# eeZeeProp.net
KiCad netlist of a schematic drawn in EAGLE
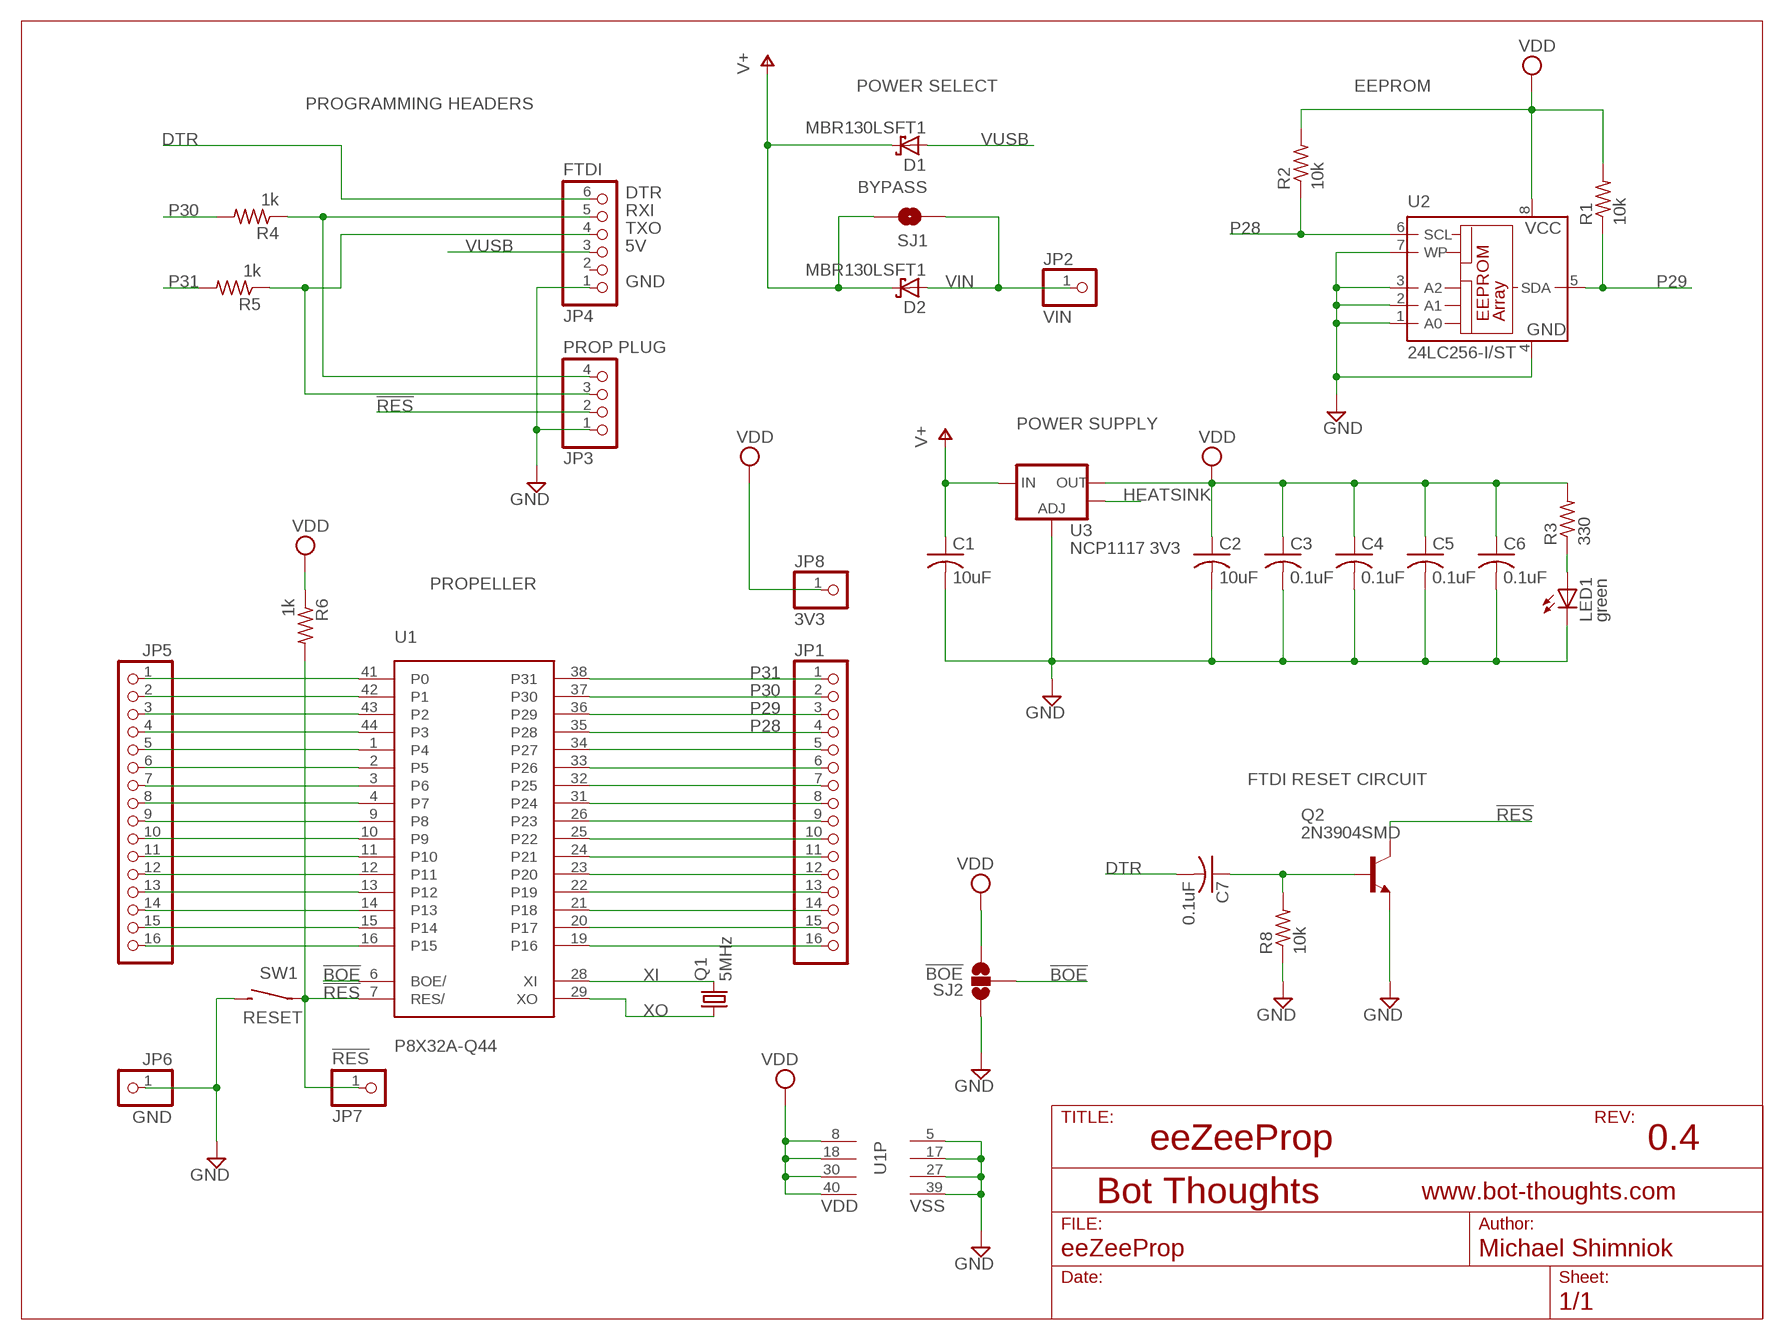
[diagram p0: schematic, sheet 1]

(export (version "E")
  (design (tool "Eeschema 10.0.6"))
  (components
    (comp (ref "C1")
      (value "10uF")
      (footprint "eagle-import:C1206")
      (fields (field (name "PARTNO") "T491A106M006AT"))
      (libsource (lib "eagle-import") (part "C-USC1206"))
    )
    (comp (ref "C2")
      (value "10uF")
      (footprint "eagle-import:C1206")
      (fields (field (name "PARTNO") "T491A106M006AT"))
      (libsource (lib "eagle-import") (part "C-USC1206"))
    )
    (comp (ref "C3")
      (value "0.1uF")
      (footprint "eagle-import:C0603")
      (fields (field (name "PARTNO") "0603YC104KAT2A"))
      (libsource (lib "eagle-import") (part "C-USC0603"))
    )
    (comp (ref "C4")
      (value "0.1uF")
      (footprint "eagle-import:C0603")
      (fields (field (name "PARTNO") "0603YC104KAT2A"))
      (libsource (lib "eagle-import") (part "C-USC0603"))
    )
    (comp (ref "C5")
      (value "0.1uF")
      (footprint "eagle-import:C0603")
      (fields (field (name "PARTNO") "0603YC104KAT2A"))
      (libsource (lib "eagle-import") (part "C-USC0603"))
    )
    (comp (ref "C6")
      (value "0.1uF")
      (footprint "eagle-import:C0603")
      (fields (field (name "PARTNO") "0603YC104KAT2A"))
      (libsource (lib "eagle-import") (part "C-USC0603"))
    )
    (comp (ref "C7")
      (value "0.1uF")
      (footprint "eagle-import:C0603")
      (fields (field (name "PARTNO") "0603YC104KAT2A"))
      (libsource (lib "eagle-import") (part "C-USC0603"))
    )
    (comp (ref "D1")
      (value "MBR130LSFT1")
      (footprint "eagle-import:SOD123FL")
      (fields (field (name "PARTNO") "MBR130LSFT1G"))
      (libsource (lib "eagle-import") (part "SCHOTTKY-DIODE-MBR130LSFT1"))
    )
    (comp (ref "D2")
      (value "MBR130LSFT1")
      (footprint "eagle-import:SOD123FL")
      (fields (field (name "PARTNO") "MBR130LSFT1G"))
      (libsource (lib "eagle-import") (part "SCHOTTKY-DIODE-MBR130LSFT1"))
    )
    (comp (ref "JP1")
      (value "PINHD-1X16_2.54-S")
      (footprint "eagle-import:1X16-S")
      (libsource (lib "eagle-import") (part "PINHD-1X16_2.54-S"))
    )
    (comp (ref "JP2")
      (value "VIN")
      (footprint "eagle-import:1X01")
      (libsource (lib "eagle-import") (part "PINHD-1X01_2.54"))
    )
    (comp (ref "JP3")
      (value "PROP PLUG")
      (footprint "eagle-import:1X04-S")
      (libsource (lib "eagle-import") (part "PINHD-1X04_2.54-S"))
    )
    (comp (ref "JP4")
      (value "FTDI")
      (footprint "eagle-import:1X06-S")
      (fields (field (name "PARTNO") "2211S-06G"))
      (libsource (lib "eagle-import") (part "PINHD-1X06_2.54-S"))
    )
    (comp (ref "JP5")
      (value "PINHD-1X16_2.54-S")
      (footprint "eagle-import:1X16-S")
      (libsource (lib "eagle-import") (part "PINHD-1X16_2.54-S"))
    )
    (comp (ref "JP6")
      (value "GND")
      (footprint "eagle-import:1X01")
      (libsource (lib "eagle-import") (part "PINHD-1X01_2.54"))
    )
    (comp (ref "JP7")
      (value "!RES")
      (footprint "eagle-import:1X01")
      (libsource (lib "eagle-import") (part "PINHD-1X01_2.54"))
    )
    (comp (ref "JP8")
      (value "3V3")
      (footprint "eagle-import:1X01")
      (libsource (lib "eagle-import") (part "PINHD-1X01_2.54"))
    )
    (comp (ref "LED1")
      (value "green")
      (footprint "eagle-import:CHIPLED_1206")
      (fields (field (name "PARTNO") "LG N971-KN-1"))
      (libsource (lib "eagle-import") (part "LEDCHIPLED_1206"))
    )
    (comp (ref "Q1")
      (value "5MHz")
      (footprint "eagle-import:HC49U-V")
      (fields (field (name "OC_FARNELL") "1666969") (field (name "PARTNO") "HC49US-5.000MABJ-UB"))
      (libsource (lib "eagle-import") (part "CRYSTALHC49U-V"))
    )
    (comp (ref "Q2")
      (value "2N3904SMD")
      (footprint "eagle-import:SOT-23")
      (fields (field (name "PARTNO") "MMBT3904LT3G"))
      (libsource (lib "eagle-import") (part "2N3904SMD"))
    )
    (comp (ref "R1")
      (value "10k")
      (footprint "eagle-import:R0603")
      (fields (field (name "PARTNO") "ERJ-3GEYJ103V"))
      (libsource (lib "eagle-import") (part "R-US_R0603"))
    )
    (comp (ref "R2")
      (value "10k")
      (footprint "eagle-import:R0603")
      (fields (field (name "PARTNO") "ERJ-3GEYJ103V"))
      (libsource (lib "eagle-import") (part "R-US_R0603"))
    )
    (comp (ref "R3")
      (value "330")
      (footprint "eagle-import:R0603")
      (fields (field (name "PARTNO") "ERJ-3GEYJ331V"))
      (libsource (lib "eagle-import") (part "R-US_R0603"))
    )
    (comp (ref "R4")
      (value "1k")
      (footprint "eagle-import:R0603")
      (fields (field (name "PARTNO") "RC0603JR-071KL"))
      (libsource (lib "eagle-import") (part "R-US_R0603"))
    )
    (comp (ref "R5")
      (value "1k")
      (footprint "eagle-import:R0603")
      (fields (field (name "PARTNO") "RC0603JR-071KL"))
      (libsource (lib "eagle-import") (part "R-US_R0603"))
    )
    (comp (ref "R6")
      (value "1k")
      (footprint "eagle-import:R0603")
      (fields (field (name "PARTNO") "RC0603JR-071KL"))
      (libsource (lib "eagle-import") (part "R-US_R0603"))
    )
    (comp (ref "R8")
      (value "10k")
      (footprint "eagle-import:R0603")
      (fields (field (name "PARTNO") "ERJ-3GEYJ103V"))
      (libsource (lib "eagle-import") (part "R-US_R0603"))
    )
    (comp (ref "SJ1")
      (value "BYPASS")
      (footprint "eagle-import:SJ_2S-NO")
      (libsource (lib "eagle-import") (part "SOLDERJUMPERNO"))
    )
    (comp (ref "SJ2")
      (value "!BOE")
      (footprint "eagle-import:SJ_3")
      (libsource (lib "eagle-import") (part "SOLDERJUMPER_2WAYS"))
    )
    (comp (ref "SW1")
      (value "RESET")
      (footprint "eagle-import:6MMTACTILE_RECT")
      (fields (field (name "PARTNO") "MJTP1243"))
      (libsource (lib "eagle-import") (part "SPST_TAC_RECT1"))
    )
    (comp (ref "U1")
      (value "P8X32A-Q44")
      (footprint "eagle-import:P8X32A-Q44")
      (fields (field (name "PARTNO") "P8X32A-Q44"))
      (libsource (lib "eagle-import") (part "P8X32A-Q44"))
    )
    (comp (ref "U2")
      (value "24LC256-I/ST")
      (footprint "eagle-import:SO-08")
      (fields
        (field (name "MF") "MICROCHIP")
        (field (name "MPN") "24LC128-I/SNG")
        (field (name "MF_1") "OnSemi")
        (field (name "MPN_1") "CAT24C256WI-GT3")
        (field (name "PARTNO") "CAT24C256WI-GT3")
      )
      (libsource (lib "eagle-import") (part "24SNLC128"))
    )
    (comp (ref "U3")
      (value "NCP1117 3V3")
      (footprint "eagle-import:SOT223")
      (fields (field (name "PARTNO") "NCP1117ST33T3G"))
      (libsource (lib "eagle-import") (part "V_REG_LM1117SOT223"))
    )
  )
  (nets
    (net (code "1") (name "/DTR") (class "Default")
      (node (ref "C7") (pin "2") (pinfunction "2_2") (pintype "passive"))
      (node (ref "JP4") (pin "6") (pinfunction "6_6") (pintype "passive"))
    )
    (net (code "2") (name "/HEATSINK") (class "Default")
      (node (ref "U3") (pin "4") (pinfunction "OUT_4") (pintype "output"))
    )
    (net (code "3") (name "/P28") (class "Default")
      (node (ref "JP1") (pin "4") (pinfunction "4_4") (pintype "passive"))
      (node (ref "R2") (pin "1") (pinfunction "1_1") (pintype "passive"))
      (node (ref "U1") (pin "35") (pinfunction "P28_35") (pintype "bidirectional"))
      (node (ref "U2") (pin "6") (pinfunction "SCL_6") (pintype "input"))
    )
    (net (code "4") (name "/P29") (class "Default")
      (node (ref "JP1") (pin "3") (pinfunction "3_3") (pintype "passive"))
      (node (ref "R1") (pin "1") (pinfunction "1_1") (pintype "passive"))
      (node (ref "U1") (pin "36") (pinfunction "P29_36") (pintype "bidirectional"))
      (node (ref "U2") (pin "5") (pinfunction "SDA_5") (pintype "bidirectional"))
    )
    (net (code "5") (name "/P30") (class "Default")
      (node (ref "JP1") (pin "2") (pinfunction "2_2") (pintype "passive"))
      (node (ref "R4") (pin "2") (pinfunction "2_2") (pintype "passive"))
      (node (ref "U1") (pin "37") (pinfunction "P30_37") (pintype "bidirectional"))
    )
    (net (code "6") (name "/P31") (class "Default")
      (node (ref "JP1") (pin "1") (pinfunction "1_1") (pintype "passive"))
      (node (ref "R5") (pin "2") (pinfunction "2_2") (pintype "passive"))
      (node (ref "U1") (pin "38") (pinfunction "P31_38") (pintype "bidirectional"))
    )
    (net (code "7") (name "/VIN") (class "Default")
      (node (ref "D2") (pin "A") (pinfunction "A_A") (pintype "passive"))
      (node (ref "JP2") (pin "1") (pinfunction "1_1") (pintype "passive"))
      (node (ref "SJ1") (pin "1") (pinfunction "1_1") (pintype "passive"))
    )
    (net (code "8") (name "/VUSB") (class "Default")
      (node (ref "D1") (pin "A") (pinfunction "A_A") (pintype "passive"))
      (node (ref "JP4") (pin "3") (pinfunction "3_3") (pintype "passive"))
    )
    (net (code "9") (name "/XI") (class "Default")
      (node (ref "Q1") (pin "2") (pinfunction "2_2") (pintype "passive"))
      (node (ref "U1") (pin "28") (pinfunction "XI_28") (pintype "input"))
    )
    (net (code "10") (name "/XO") (class "Default")
      (node (ref "Q1") (pin "1") (pinfunction "1_1") (pintype "passive"))
      (node (ref "U1") (pin "29") (pinfunction "XO_29") (pintype "output"))
    )
    (net (code "11") (name "/~{BOE}") (class "Default")
      (node (ref "SJ2") (pin "2") (pinfunction "2_2") (pintype "passive"))
      (node (ref "U1") (pin "6") (pinfunction "BOE/_6") (pintype "input"))
    )
    (net (code "12") (name "/~{RES}") (class "Default")
      (node (ref "JP3") (pin "2") (pinfunction "2_2") (pintype "passive"))
      (node (ref "JP7") (pin "1") (pinfunction "1_1") (pintype "passive"))
      (node (ref "Q2") (pin "1") (pinfunction "C_1") (pintype "passive"))
      (node (ref "R6") (pin "2") (pinfunction "2_2") (pintype "passive"))
      (node (ref "SW1") (pin "P$1") (pinfunction "P_P$1") (pintype "passive"))
      (node (ref "U1") (pin "7") (pinfunction "RES/_7") (pintype "bidirectional"))
    )
    (net (code "13") (name "GND") (class "Default")
      (node (ref "C1") (pin "2") (pinfunction "2_2") (pintype "passive"))
      (node (ref "C2") (pin "2") (pinfunction "2_2") (pintype "passive"))
      (node (ref "C3") (pin "2") (pinfunction "2_2") (pintype "passive"))
      (node (ref "C4") (pin "2") (pinfunction "2_2") (pintype "passive"))
      (node (ref "C5") (pin "2") (pinfunction "2_2") (pintype "passive"))
      (node (ref "C6") (pin "2") (pinfunction "2_2") (pintype "passive"))
      (node (ref "JP3") (pin "1") (pinfunction "1_1") (pintype "passive"))
      (node (ref "JP4") (pin "1") (pinfunction "1_1") (pintype "passive"))
      (node (ref "JP6") (pin "1") (pinfunction "1_1") (pintype "passive"))
      (node (ref "LED1") (pin "C") (pinfunction "C_C") (pintype "passive"))
      (node (ref "Q2") (pin "2") (pinfunction "E_2") (pintype "passive"))
      (node (ref "R8") (pin "1") (pinfunction "1_1") (pintype "passive"))
      (node (ref "SJ2") (pin "1") (pinfunction "1_1") (pintype "passive"))
      (node (ref "SW1") (pin "P$2") (pinfunction "S_P$2") (pintype "passive"))
      (node (ref "U1") (pin "17") (pinfunction "VSS_17") (pintype "power_in"))
      (node (ref "U1") (pin "27") (pinfunction "VSS_27") (pintype "power_in"))
      (node (ref "U1") (pin "39") (pinfunction "VSS_39") (pintype "power_in"))
      (node (ref "U1") (pin "5") (pinfunction "VSS_5") (pintype "power_in"))
      (node (ref "U2") (pin "1") (pinfunction "A0_1") (pintype "input"))
      (node (ref "U2") (pin "2") (pinfunction "A1_2") (pintype "input"))
      (node (ref "U2") (pin "3") (pinfunction "A2_3") (pintype "input"))
      (node (ref "U2") (pin "4") (pinfunction "GND_4") (pintype "power_in"))
      (node (ref "U2") (pin "7") (pinfunction "WP_7") (pintype "input"))
      (node (ref "U3") (pin "1") (pinfunction "ADJ_1") (pintype "input"))
    )
    (net (code "14") (name "Net-(JP3-Pad3)") (class "Default")
      (node (ref "JP3") (pin "3") (pinfunction "3_3") (pintype "passive"))
      (node (ref "JP4") (pin "4") (pinfunction "4_4") (pintype "passive"))
      (node (ref "R5") (pin "1") (pinfunction "1_1") (pintype "passive"))
    )
    (net (code "15") (name "Net-(JP3-Pad4)") (class "Default")
      (node (ref "JP3") (pin "4") (pinfunction "4_4") (pintype "passive"))
      (node (ref "JP4") (pin "5") (pinfunction "5_5") (pintype "passive"))
      (node (ref "R4") (pin "1") (pinfunction "1_1") (pintype "passive"))
    )
    (net (code "16") (name "Net-(LED1-PadA)") (class "Default")
      (node (ref "LED1") (pin "A") (pinfunction "A_A") (pintype "passive"))
      (node (ref "R3") (pin "1") (pinfunction "1_1") (pintype "passive"))
    )
    (net (code "17") (name "Net-(Q2-B)") (class "Default")
      (node (ref "C7") (pin "1") (pinfunction "1_1") (pintype "passive"))
      (node (ref "Q2") (pin "3") (pinfunction "B_3") (pintype "passive"))
      (node (ref "R8") (pin "2") (pinfunction "2_2") (pintype "passive"))
    )
    (net (code "18") (name "Net-(U1B-P0)") (class "Default")
      (node (ref "JP5") (pin "1") (pinfunction "1_1") (pintype "passive"))
      (node (ref "U1") (pin "41") (pinfunction "P0_41") (pintype "bidirectional"))
    )
    (net (code "19") (name "Net-(U1B-P1)") (class "Default")
      (node (ref "JP5") (pin "2") (pinfunction "2_2") (pintype "passive"))
      (node (ref "U1") (pin "42") (pinfunction "P1_42") (pintype "bidirectional"))
    )
    (net (code "20") (name "Net-(U1B-P2)") (class "Default")
      (node (ref "JP5") (pin "3") (pinfunction "3_3") (pintype "passive"))
      (node (ref "U1") (pin "43") (pinfunction "P2_43") (pintype "bidirectional"))
    )
    (net (code "21") (name "Net-(U1B-P3)") (class "Default")
      (node (ref "JP5") (pin "4") (pinfunction "4_4") (pintype "passive"))
      (node (ref "U1") (pin "44") (pinfunction "P3_44") (pintype "bidirectional"))
    )
    (net (code "22") (name "Net-(U1B-P4)") (class "Default")
      (node (ref "JP5") (pin "5") (pinfunction "5_5") (pintype "passive"))
      (node (ref "U1") (pin "1") (pinfunction "P4_1") (pintype "bidirectional"))
    )
    (net (code "23") (name "Net-(U1B-P5)") (class "Default")
      (node (ref "JP5") (pin "6") (pinfunction "6_6") (pintype "passive"))
      (node (ref "U1") (pin "2") (pinfunction "P5_2") (pintype "bidirectional"))
    )
    (net (code "24") (name "Net-(U1B-P6)") (class "Default")
      (node (ref "JP5") (pin "7") (pinfunction "7_7") (pintype "passive"))
      (node (ref "U1") (pin "3") (pinfunction "P6_3") (pintype "bidirectional"))
    )
    (net (code "25") (name "Net-(U1B-P7)") (class "Default")
      (node (ref "JP5") (pin "8") (pinfunction "8_8") (pintype "passive"))
      (node (ref "U1") (pin "4") (pinfunction "P7_4") (pintype "bidirectional"))
    )
    (net (code "26") (name "Net-(U1B-P8)") (class "Default")
      (node (ref "JP5") (pin "9") (pinfunction "9_9") (pintype "passive"))
      (node (ref "U1") (pin "9") (pinfunction "P8_9") (pintype "bidirectional"))
    )
    (net (code "27") (name "Net-(U1B-P9)") (class "Default")
      (node (ref "JP5") (pin "10") (pinfunction "10_10") (pintype "passive"))
      (node (ref "U1") (pin "10") (pinfunction "P9_10") (pintype "bidirectional"))
    )
    (net (code "28") (name "Net-(U1B-P10)") (class "Default")
      (node (ref "JP5") (pin "11") (pinfunction "11_11") (pintype "passive"))
      (node (ref "U1") (pin "11") (pinfunction "P10_11") (pintype "bidirectional"))
    )
    (net (code "29") (name "Net-(U1B-P11)") (class "Default")
      (node (ref "JP5") (pin "12") (pinfunction "12_12") (pintype "passive"))
      (node (ref "U1") (pin "12") (pinfunction "P11_12") (pintype "bidirectional"))
    )
    (net (code "30") (name "Net-(U1B-P12)") (class "Default")
      (node (ref "JP5") (pin "13") (pinfunction "13_13") (pintype "passive"))
      (node (ref "U1") (pin "13") (pinfunction "P12_13") (pintype "bidirectional"))
    )
    (net (code "31") (name "Net-(U1B-P13)") (class "Default")
      (node (ref "JP5") (pin "14") (pinfunction "14_14") (pintype "passive"))
      (node (ref "U1") (pin "14") (pinfunction "P13_14") (pintype "bidirectional"))
    )
    (net (code "32") (name "Net-(U1B-P14)") (class "Default")
      (node (ref "JP5") (pin "15") (pinfunction "15_15") (pintype "passive"))
      (node (ref "U1") (pin "15") (pinfunction "P14_15") (pintype "bidirectional"))
    )
    (net (code "33") (name "Net-(U1B-P15)") (class "Default")
      (node (ref "JP5") (pin "16") (pinfunction "16_16") (pintype "passive"))
      (node (ref "U1") (pin "16") (pinfunction "P15_16") (pintype "bidirectional"))
    )
    (net (code "34") (name "Net-(U1B-P16)") (class "Default")
      (node (ref "JP1") (pin "16") (pinfunction "16_16") (pintype "passive"))
      (node (ref "U1") (pin "19") (pinfunction "P16_19") (pintype "bidirectional"))
    )
    (net (code "35") (name "Net-(U1B-P17)") (class "Default")
      (node (ref "JP1") (pin "15") (pinfunction "15_15") (pintype "passive"))
      (node (ref "U1") (pin "20") (pinfunction "P17_20") (pintype "bidirectional"))
    )
    (net (code "36") (name "Net-(U1B-P18)") (class "Default")
      (node (ref "JP1") (pin "14") (pinfunction "14_14") (pintype "passive"))
      (node (ref "U1") (pin "21") (pinfunction "P18_21") (pintype "bidirectional"))
    )
    (net (code "37") (name "Net-(U1B-P19)") (class "Default")
      (node (ref "JP1") (pin "13") (pinfunction "13_13") (pintype "passive"))
      (node (ref "U1") (pin "22") (pinfunction "P19_22") (pintype "bidirectional"))
    )
    (net (code "38") (name "Net-(U1B-P20)") (class "Default")
      (node (ref "JP1") (pin "12") (pinfunction "12_12") (pintype "passive"))
      (node (ref "U1") (pin "23") (pinfunction "P20_23") (pintype "bidirectional"))
    )
    (net (code "39") (name "Net-(U1B-P21)") (class "Default")
      (node (ref "JP1") (pin "11") (pinfunction "11_11") (pintype "passive"))
      (node (ref "U1") (pin "24") (pinfunction "P21_24") (pintype "bidirectional"))
    )
    (net (code "40") (name "Net-(U1B-P22)") (class "Default")
      (node (ref "JP1") (pin "10") (pinfunction "10_10") (pintype "passive"))
      (node (ref "U1") (pin "25") (pinfunction "P22_25") (pintype "bidirectional"))
    )
    (net (code "41") (name "Net-(U1B-P23)") (class "Default")
      (node (ref "JP1") (pin "9") (pinfunction "9_9") (pintype "passive"))
      (node (ref "U1") (pin "26") (pinfunction "P23_26") (pintype "bidirectional"))
    )
    (net (code "42") (name "Net-(U1B-P24)") (class "Default")
      (node (ref "JP1") (pin "8") (pinfunction "8_8") (pintype "passive"))
      (node (ref "U1") (pin "31") (pinfunction "P24_31") (pintype "bidirectional"))
    )
    (net (code "43") (name "Net-(U1B-P25)") (class "Default")
      (node (ref "JP1") (pin "7") (pinfunction "7_7") (pintype "passive"))
      (node (ref "U1") (pin "32") (pinfunction "P25_32") (pintype "bidirectional"))
    )
    (net (code "44") (name "Net-(U1B-P26)") (class "Default")
      (node (ref "JP1") (pin "6") (pinfunction "6_6") (pintype "passive"))
      (node (ref "U1") (pin "33") (pinfunction "P26_33") (pintype "bidirectional"))
    )
    (net (code "45") (name "Net-(U1B-P27)") (class "Default")
      (node (ref "JP1") (pin "5") (pinfunction "5_5") (pintype "passive"))
      (node (ref "U1") (pin "34") (pinfunction "P27_34") (pintype "bidirectional"))
    )
    (net (code "46") (name "V+") (class "Default")
      (node (ref "C1") (pin "1") (pinfunction "1_1") (pintype "passive"))
      (node (ref "D1") (pin "C") (pinfunction "C_C") (pintype "passive"))
      (node (ref "D2") (pin "C") (pinfunction "C_C") (pintype "passive"))
      (node (ref "SJ1") (pin "2") (pinfunction "2_2") (pintype "passive"))
      (node (ref "U3") (pin "3") (pinfunction "IN_3") (pintype "input"))
    )
    (net (code "47") (name "VDD") (class "Default")
      (node (ref "C2") (pin "1") (pinfunction "1_1") (pintype "passive"))
      (node (ref "C3") (pin "1") (pinfunction "1_1") (pintype "passive"))
      (node (ref "C4") (pin "1") (pinfunction "1_1") (pintype "passive"))
      (node (ref "C5") (pin "1") (pinfunction "1_1") (pintype "passive"))
      (node (ref "C6") (pin "1") (pinfunction "1_1") (pintype "passive"))
      (node (ref "JP8") (pin "1") (pinfunction "1_1") (pintype "passive"))
      (node (ref "R1") (pin "2") (pinfunction "2_2") (pintype "passive"))
      (node (ref "R2") (pin "2") (pinfunction "2_2") (pintype "passive"))
      (node (ref "R3") (pin "2") (pinfunction "2_2") (pintype "passive"))
      (node (ref "R6") (pin "1") (pinfunction "1_1") (pintype "passive"))
      (node (ref "SJ2") (pin "3") (pinfunction "3_3") (pintype "passive"))
      (node (ref "U1") (pin "18") (pinfunction "VDD_18") (pintype "power_in"))
      (node (ref "U1") (pin "30") (pinfunction "VDD_30") (pintype "power_in"))
      (node (ref "U1") (pin "40") (pinfunction "VDD_40") (pintype "power_in"))
      (node (ref "U1") (pin "8") (pinfunction "VDD_8") (pintype "power_in"))
      (node (ref "U2") (pin "8") (pinfunction "VCC_8") (pintype "power_in"))
      (node (ref "U3") (pin "2") (pinfunction "OUT_2") (pintype "output"))
    )
    (net (code "48") (name "unconnected-(JP4-Pad2)") (class "Default")
      (node (ref "JP4") (pin "2") (pinfunction "2_2") (pintype "passive"))
    )
  )
)
